# schema.net
KiCad netlist of a schematic drawn in Altium Designer
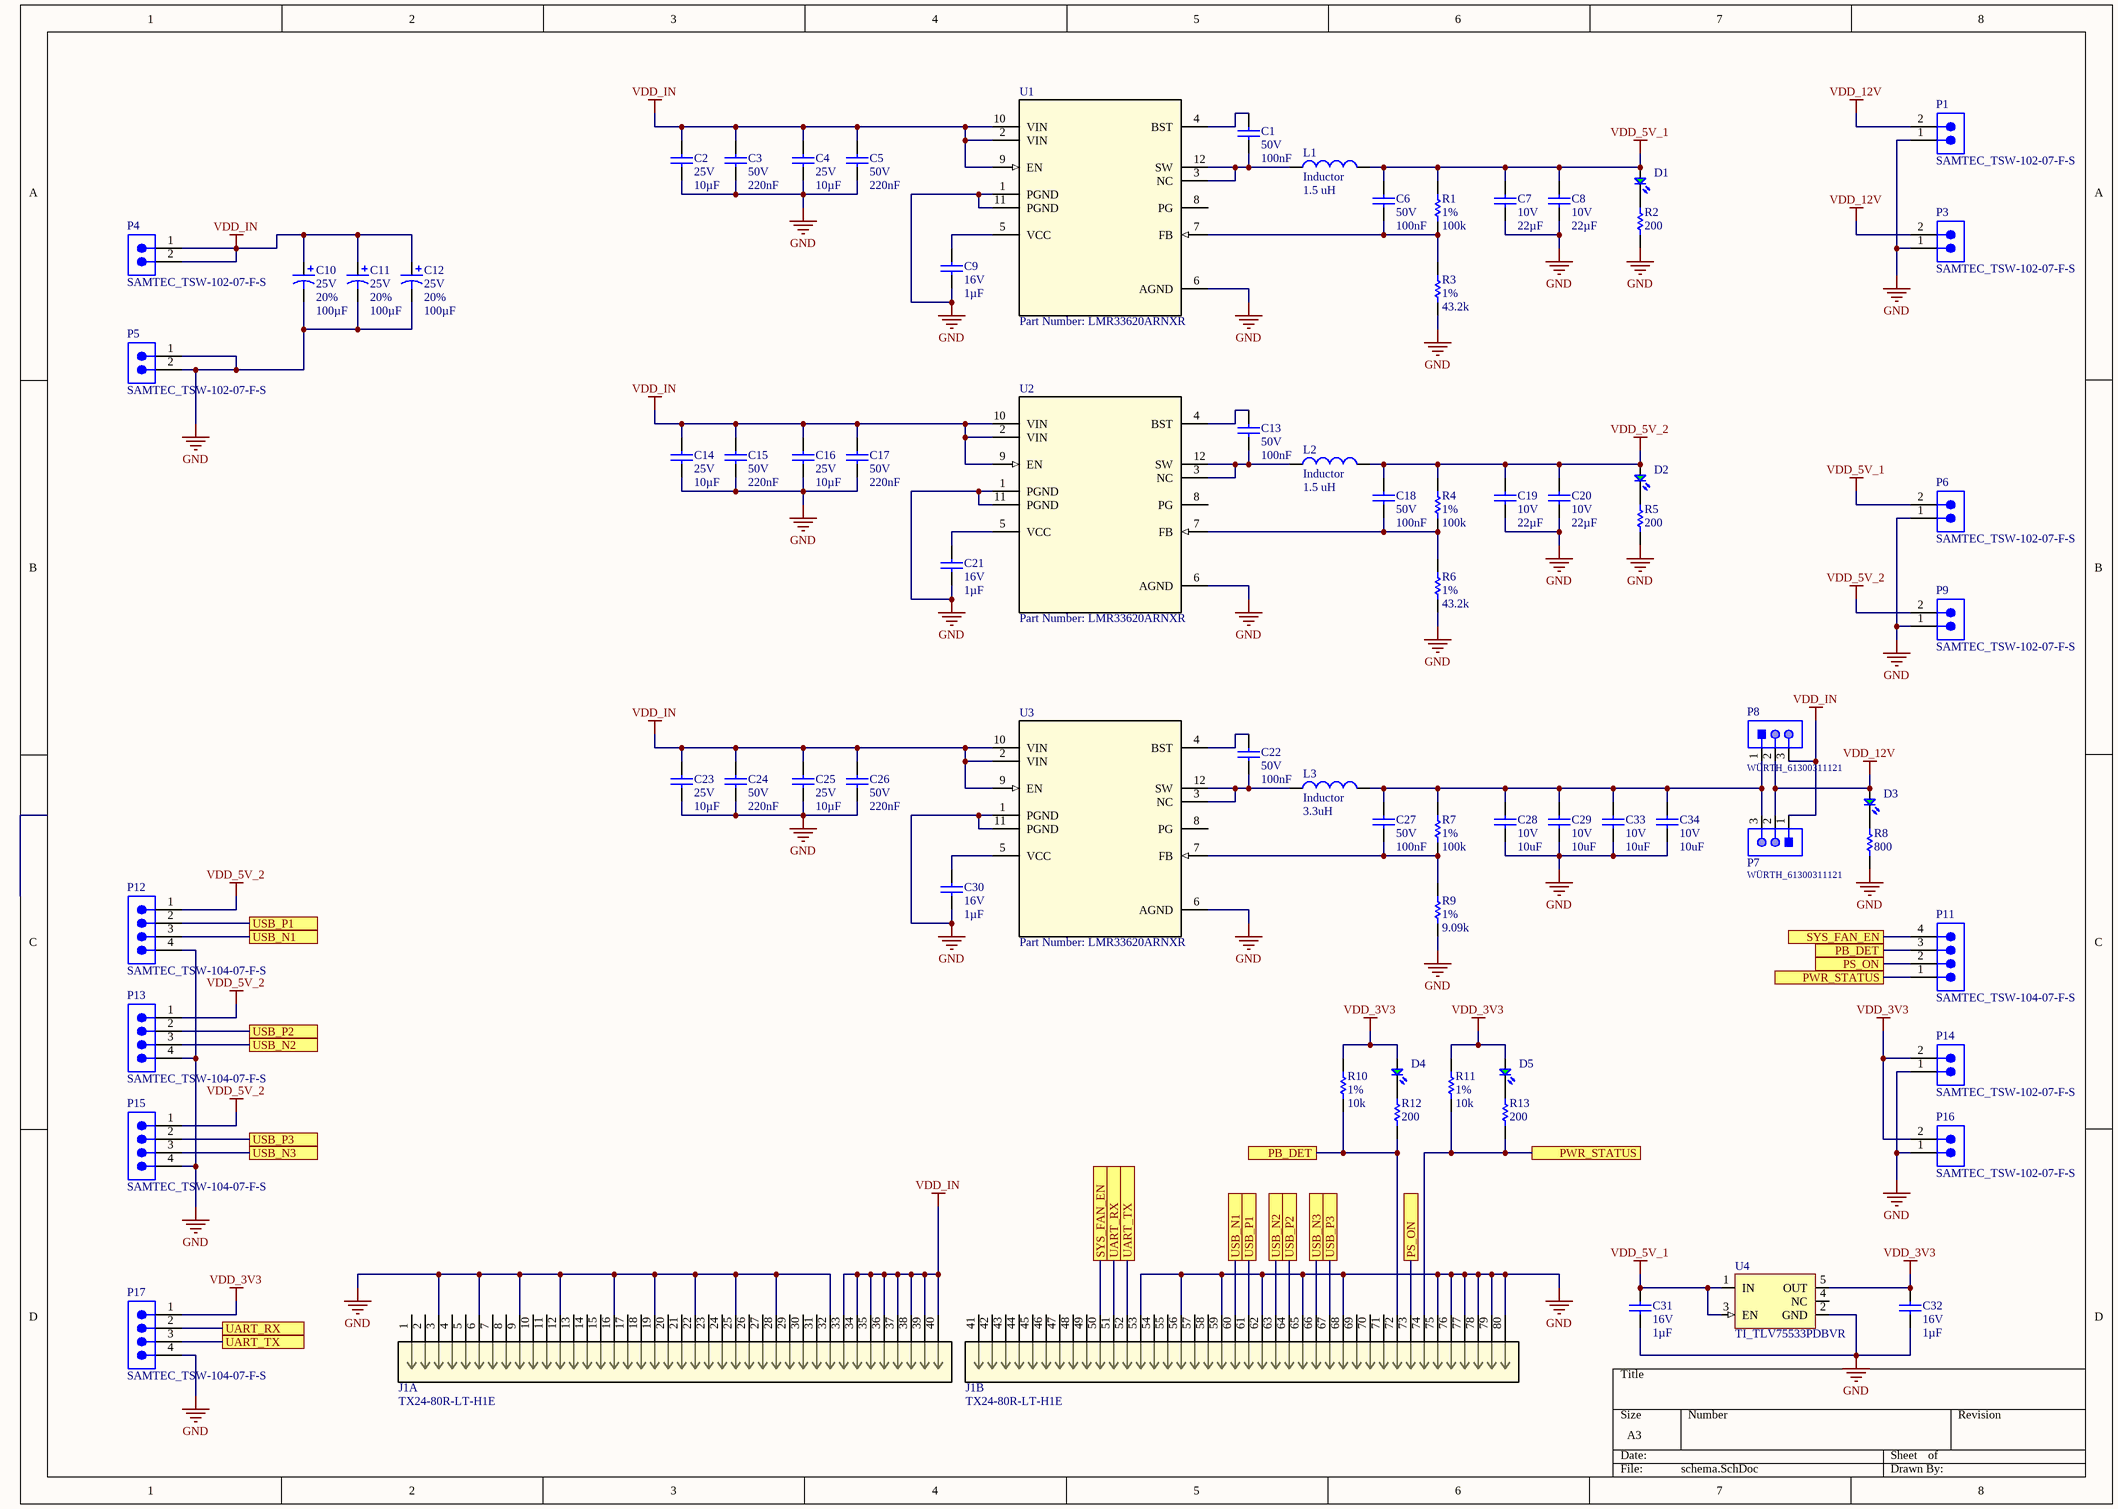
[diagram p0: schema.SchDoc]

(export (version "E")
  (design (tool "Eeschema 10.0.6"))
  (components
    (comp (ref "C1")
      (value "CAP MLCC 100nF 0402 10% 50V X5R")
      (footprint "C0402N")
      (description "Capacitor, MLCC, 100nF, 0402, 10%, 50V, X5R")
      (fields (field (name "VOLTAGE RATING") "50V") (field (name "COMPONENT VALUE") "100nF"))
      (libsource (lib "Ctek Sweden AB") (part "Non-polarised Capacitor"))
    )
    (comp (ref "C2")
      (value "CAP MLCC 10uF 0805 10% 25V X5R")
      (footprint "C0805N")
      (description "Capacitor, MLCC, 10uF, 0805, 10%, 25V, X5R")
      (fields (field (name "VOLTAGE RATING") "25V") (field (name "COMPONENT VALUE") "10µF"))
      (libsource (lib "Ctek Sweden AB") (part "Non-polarised Capacitor"))
    )
    (comp (ref "C3")
      (value "CAP MLCC 100nF 0402 10% 50V X5R")
      (footprint "C0402N")
      (description "Capacitor, MLCC, 100nF, 0402, 10%, 50V, X5R")
      (fields (field (name "VOLTAGE RATING") "50V") (field (name "COMPONENT VALUE") "220nF"))
      (libsource (lib "Ctek Sweden AB") (part "Non-polarised Capacitor"))
    )
    (comp (ref "C4")
      (value "CAP MLCC 10uF 0805 10% 25V X5R")
      (footprint "C0805N")
      (description "Capacitor, MLCC, 10uF, 0805, 10%, 25V, X5R")
      (fields (field (name "VOLTAGE RATING") "25V") (field (name "COMPONENT VALUE") "10µF"))
      (libsource (lib "Ctek Sweden AB") (part "Non-polarised Capacitor"))
    )
    (comp (ref "C5")
      (value "CAP MLCC 100nF 0402 10% 50V X5R")
      (footprint "C0402N")
      (description "Capacitor, MLCC, 100nF, 0402, 10%, 50V, X5R")
      (fields (field (name "VOLTAGE RATING") "50V") (field (name "COMPONENT VALUE") "220nF"))
      (libsource (lib "Ctek Sweden AB") (part "Non-polarised Capacitor"))
    )
    (comp (ref "C6")
      (value "CAP MLCC 100nF 0402 10% 50V X5R")
      (footprint "C0402N")
      (description "Capacitor, MLCC, 100nF, 0402, 10%, 50V, X5R")
      (fields (field (name "VOLTAGE RATING") "50V") (field (name "COMPONENT VALUE") "100nF"))
      (libsource (lib "Ctek Sweden AB") (part "Non-polarised Capacitor"))
    )
    (comp (ref "C7")
      (value "CAP MLCC 22uF 0805 10% 10V X5R")
      (footprint "C0805N")
      (description "Capacitor, MLCC, 22uF, 0805, 10%, 10V, X5R")
      (fields (field (name "VOLTAGE RATING") "10V") (field (name "COMPONENT VALUE") "22µF"))
      (libsource (lib "Ctek Sweden AB") (part "Non-polarised Capacitor"))
    )
    (comp (ref "C8")
      (value "CAP MLCC 22uF 0805 10% 10V X5R")
      (footprint "C0805N")
      (description "Capacitor, MLCC, 22uF, 0805, 10%, 10V, X5R")
      (fields (field (name "VOLTAGE RATING") "10V") (field (name "COMPONENT VALUE") "22µF"))
      (libsource (lib "Ctek Sweden AB") (part "Non-polarised Capacitor"))
    )
    (comp (ref "C9")
      (value "CAP MLCC 1uF 0402 10% 16V X5R")
      (footprint "C0402N")
      (description "Capacitor, MLCC, 1uF, 0402, 10%, 16V, X5R")
      (fields (field (name "VOLTAGE RATING") "16V") (field (name "COMPONENT VALUE") "1µF"))
      (libsource (lib "Ctek Sweden AB") (part "Non-polarised Capacitor"))
    )
    (comp (ref "C10")
      (value "ECAP 100uF radial 20% 25V 0.7mohm")
      (footprint "New footprint 1")
      (description "Electrolytic capacitor, 100uF, radial, 20%, 25V, 0.7mohm")
      (fields
        (field (name "VOLTAGE RATING") "25V")
        (field (name "COMPONENT TOLERANCE") "20%")
        (field (name "COMPONENT VALUE") "100µF")
      )
      (libsource (lib "Ctek Sweden AB") (part "Polarised Capacitor"))
    )
    (comp (ref "C11")
      (value "ECAP 100uF radial 20% 25V 0.7mohm")
      (footprint "New footprint 1")
      (description "Electrolytic capacitor, 100uF, radial, 20%, 25V, 0.7mohm")
      (fields
        (field (name "VOLTAGE RATING") "25V")
        (field (name "COMPONENT TOLERANCE") "20%")
        (field (name "COMPONENT VALUE") "100µF")
      )
      (libsource (lib "Ctek Sweden AB") (part "Polarised Capacitor"))
    )
    (comp (ref "C12")
      (value "ECAP 100uF radial 20% 25V 0.7mohm")
      (footprint "New footprint 1")
      (description "Electrolytic capacitor, 100uF, radial, 20%, 25V, 0.7mohm")
      (fields
        (field (name "VOLTAGE RATING") "25V")
        (field (name "COMPONENT TOLERANCE") "20%")
        (field (name "COMPONENT VALUE") "100µF")
      )
      (libsource (lib "Ctek Sweden AB") (part "Polarised Capacitor"))
    )
    (comp (ref "C13")
      (value "CAP MLCC 100nF 0402 10% 50V X5R")
      (footprint "C0402N")
      (description "Capacitor, MLCC, 100nF, 0402, 10%, 50V, X5R")
      (fields (field (name "VOLTAGE RATING") "50V") (field (name "COMPONENT VALUE") "100nF"))
      (libsource (lib "Ctek Sweden AB") (part "Non-polarised Capacitor"))
    )
    (comp (ref "C14")
      (value "CAP MLCC 10uF 0805 10% 25V X5R")
      (footprint "C0805N")
      (description "Capacitor, MLCC, 10uF, 0805, 10%, 25V, X5R")
      (fields (field (name "VOLTAGE RATING") "25V") (field (name "COMPONENT VALUE") "10µF"))
      (libsource (lib "Ctek Sweden AB") (part "Non-polarised Capacitor"))
    )
    (comp (ref "C15")
      (value "CAP MLCC 100nF 0402 10% 50V X5R")
      (footprint "C0402N")
      (description "Capacitor, MLCC, 100nF, 0402, 10%, 50V, X5R")
      (fields (field (name "VOLTAGE RATING") "50V") (field (name "COMPONENT VALUE") "220nF"))
      (libsource (lib "Ctek Sweden AB") (part "Non-polarised Capacitor"))
    )
    (comp (ref "C16")
      (value "CAP MLCC 10uF 0805 10% 25V X5R")
      (footprint "C0805N")
      (description "Capacitor, MLCC, 10uF, 0805, 10%, 25V, X5R")
      (fields (field (name "VOLTAGE RATING") "25V") (field (name "COMPONENT VALUE") "10µF"))
      (libsource (lib "Ctek Sweden AB") (part "Non-polarised Capacitor"))
    )
    (comp (ref "C17")
      (value "CAP MLCC 100nF 0402 10% 50V X5R")
      (footprint "C0402N")
      (description "Capacitor, MLCC, 100nF, 0402, 10%, 50V, X5R")
      (fields (field (name "VOLTAGE RATING") "50V") (field (name "COMPONENT VALUE") "220nF"))
      (libsource (lib "Ctek Sweden AB") (part "Non-polarised Capacitor"))
    )
    (comp (ref "C18")
      (value "CAP MLCC 100nF 0402 10% 50V X5R")
      (footprint "C0402N")
      (description "Capacitor, MLCC, 100nF, 0402, 10%, 50V, X5R")
      (fields (field (name "VOLTAGE RATING") "50V") (field (name "COMPONENT VALUE") "100nF"))
      (libsource (lib "Ctek Sweden AB") (part "Non-polarised Capacitor"))
    )
    (comp (ref "C19")
      (value "CAP MLCC 22uF 0805 10% 10V X5R")
      (footprint "C0805N")
      (description "Capacitor, MLCC, 22uF, 0805, 10%, 10V, X5R")
      (fields (field (name "VOLTAGE RATING") "10V") (field (name "COMPONENT VALUE") "22µF"))
      (libsource (lib "Ctek Sweden AB") (part "Non-polarised Capacitor"))
    )
    (comp (ref "C20")
      (value "CAP MLCC 22uF 0805 10% 10V X5R")
      (footprint "C0805N")
      (description "Capacitor, MLCC, 22uF, 0805, 10%, 10V, X5R")
      (fields (field (name "VOLTAGE RATING") "10V") (field (name "COMPONENT VALUE") "22µF"))
      (libsource (lib "Ctek Sweden AB") (part "Non-polarised Capacitor"))
    )
    (comp (ref "C21")
      (value "CAP MLCC 1uF 0402 10% 16V X5R")
      (footprint "C0402N")
      (description "Capacitor, MLCC, 1uF, 0402, 10%, 16V, X5R")
      (fields (field (name "VOLTAGE RATING") "16V") (field (name "COMPONENT VALUE") "1µF"))
      (libsource (lib "Ctek Sweden AB") (part "Non-polarised Capacitor"))
    )
    (comp (ref "C22")
      (value "CAP MLCC 100nF 0402 10% 50V X5R")
      (footprint "C0402N")
      (description "Capacitor, MLCC, 100nF, 0402, 10%, 50V, X5R")
      (fields (field (name "VOLTAGE RATING") "50V") (field (name "COMPONENT VALUE") "100nF"))
      (libsource (lib "Ctek Sweden AB") (part "Non-polarised Capacitor"))
    )
    (comp (ref "C23")
      (value "CAP MLCC 10uF 0805 10% 25V X5R")
      (footprint "C0805N")
      (description "Capacitor, MLCC, 10uF, 0805, 10%, 25V, X5R")
      (fields (field (name "VOLTAGE RATING") "25V") (field (name "COMPONENT VALUE") "10µF"))
      (libsource (lib "Ctek Sweden AB") (part "Non-polarised Capacitor"))
    )
    (comp (ref "C24")
      (value "CAP MLCC 100nF 0402 10% 50V X5R")
      (footprint "C0402N")
      (description "Capacitor, MLCC, 100nF, 0402, 10%, 50V, X5R")
      (fields (field (name "VOLTAGE RATING") "50V") (field (name "COMPONENT VALUE") "220nF"))
      (libsource (lib "Ctek Sweden AB") (part "Non-polarised Capacitor"))
    )
    (comp (ref "C25")
      (value "CAP MLCC 10uF 0805 10% 25V X5R")
      (footprint "C0805N")
      (description "Capacitor, MLCC, 10uF, 0805, 10%, 25V, X5R")
      (fields (field (name "VOLTAGE RATING") "25V") (field (name "COMPONENT VALUE") "10µF"))
      (libsource (lib "Ctek Sweden AB") (part "Non-polarised Capacitor"))
    )
    (comp (ref "C26")
      (value "CAP MLCC 100nF 0402 10% 50V X5R")
      (footprint "C0402N")
      (description "Capacitor, MLCC, 100nF, 0402, 10%, 50V, X5R")
      (fields (field (name "VOLTAGE RATING") "50V") (field (name "COMPONENT VALUE") "220nF"))
      (libsource (lib "Ctek Sweden AB") (part "Non-polarised Capacitor"))
    )
    (comp (ref "C27")
      (value "CAP MLCC 100nF 0402 10% 50V X5R")
      (footprint "C0402N")
      (description "Capacitor, MLCC, 100nF, 0402, 10%, 50V, X5R")
      (fields (field (name "VOLTAGE RATING") "50V") (field (name "COMPONENT VALUE") "100nF"))
      (libsource (lib "Ctek Sweden AB") (part "Non-polarised Capacitor"))
    )
    (comp (ref "C28")
      (value "CAP MLCC 22uF 0805 10% 10V X5R")
      (footprint "C0805N")
      (description "Capacitor, MLCC, 22uF, 0805, 10%, 10V, X5R")
      (fields (field (name "VOLTAGE RATING") "10V") (field (name "COMPONENT VALUE") "10uF"))
      (libsource (lib "Ctek Sweden AB") (part "Non-polarised Capacitor"))
    )
    (comp (ref "C29")
      (value "CAP MLCC 22uF 0805 10% 10V X5R")
      (footprint "C0805N")
      (description "Capacitor, MLCC, 22uF, 0805, 10%, 10V, X5R")
      (fields (field (name "VOLTAGE RATING") "10V") (field (name "COMPONENT VALUE") "10uF"))
      (libsource (lib "Ctek Sweden AB") (part "Non-polarised Capacitor"))
    )
    (comp (ref "C30")
      (value "CAP MLCC 1uF 0402 10% 16V X5R")
      (footprint "C0402N")
      (description "Capacitor, MLCC, 1uF, 0402, 10%, 16V, X5R")
      (fields (field (name "VOLTAGE RATING") "16V") (field (name "COMPONENT VALUE") "1µF"))
      (libsource (lib "Ctek Sweden AB") (part "Non-polarised Capacitor"))
    )
    (comp (ref "C31")
      (value "CAP MLCC 1uF 0402 10% 16V X5R")
      (footprint "C0402N")
      (description "Capacitor, MLCC, 1uF, 0402, 10%, 16V, X5R")
      (fields (field (name "VOLTAGE RATING") "16V") (field (name "COMPONENT VALUE") "1µF"))
      (libsource (lib "Ctek Sweden AB") (part "Non-polarised Capacitor"))
    )
    (comp (ref "C32")
      (value "CAP MLCC 1uF 0402 10% 16V X5R")
      (footprint "C0402N")
      (description "Capacitor, MLCC, 1uF, 0402, 10%, 16V, X5R")
      (fields (field (name "VOLTAGE RATING") "16V") (field (name "COMPONENT VALUE") "1µF"))
      (libsource (lib "Ctek Sweden AB") (part "Non-polarised Capacitor"))
    )
    (comp (ref "C33")
      (value "CAP MLCC 22uF 0805 10% 10V X5R")
      (footprint "C0805N")
      (description "Capacitor, MLCC, 22uF, 0805, 10%, 10V, X5R")
      (fields (field (name "VOLTAGE RATING") "10V") (field (name "COMPONENT VALUE") "10uF"))
      (libsource (lib "Ctek Sweden AB") (part "Non-polarised Capacitor"))
    )
    (comp (ref "C34")
      (value "CAP MLCC 22uF 0805 10% 10V X5R")
      (footprint "C0805N")
      (description "Capacitor, MLCC, 22uF, 0805, 10%, 10V, X5R")
      (fields (field (name "VOLTAGE RATING") "10V") (field (name "COMPONENT VALUE") "10uF"))
      (libsource (lib "Ctek Sweden AB") (part "Non-polarised Capacitor"))
    )
    (comp (ref "D1")
      (value "Hongbright_H2214AG72E0Z01")
      (footprint "New footprint 1")
      (description "Green LED, VFmax 3.6V")
      (libsource (lib "Ctek Sweden AB") (part "New symbol 1"))
    )
    (comp (ref "D2")
      (value "Hongbright_H2214AG72E0Z01")
      (footprint "New footprint 1")
      (description "Green LED, VFmax 3.6V")
      (libsource (lib "Ctek Sweden AB") (part "New symbol 1"))
    )
    (comp (ref "D3")
      (value "Hongbright_H2214AG72E0Z01")
      (footprint "New footprint 1")
      (description "Green LED, VFmax 3.6V")
      (libsource (lib "Ctek Sweden AB") (part "New symbol 1"))
    )
    (comp (ref "D4")
      (value "Hongbright_H2214AG72E0Z01")
      (footprint "New footprint 1")
      (description "Green LED, VFmax 3.6V")
      (libsource (lib "Ctek Sweden AB") (part "New symbol 1"))
    )
    (comp (ref "D5")
      (value "Hongbright_H2214AG72E0Z01")
      (footprint "New footprint 1")
      (description "Green LED, VFmax 3.6V")
      (libsource (lib "Ctek Sweden AB") (part "New symbol 1"))
    )
    (comp (ref "J1")
      (value "TX24-80R-LT-H1E")
      (footprint "CON80_2X40_MR_TX24_JAE")
      (description "No Description Available")
      (fields (field (name "COPYRIGHT") "Copyright (C) 2018 Accelerated Designs. All rights reserved"))
      (libsource (lib "tx24") (part "TX24-80R-LT-H1E"))
    )
    (comp (ref "L1")
      (value "Inductor")
      (footprint "INDC2016X10N")
      (fields (field (name "ALTIUM_VALUE") "1.5 uH") (field (name "PUBLISHER") "Altium Limited"))
      (libsource (lib "Miscellaneous Devices") (part "Inductor"))
    )
    (comp (ref "L2")
      (value "Inductor")
      (footprint "INDC2016X10N")
      (fields (field (name "ALTIUM_VALUE") "1.5 uH") (field (name "PUBLISHER") "Altium Limited"))
      (libsource (lib "Miscellaneous Devices") (part "Inductor"))
    )
    (comp (ref "L3")
      (value "Inductor")
      (footprint "INDC2016X10N")
      (fields (field (name "ALTIUM_VALUE") "3.3uH") (field (name "PUBLISHER") "Altium Limited"))
      (libsource (lib "Miscellaneous Devices") (part "Inductor"))
    )
    (comp (ref "P1")
      (value "SAMTEC_TSW-102-07-F-S")
      (footprint "SAMTEC-TSW-102-07-X-S")
      (description "CONN HEADER VERT 2POS 2.54MM")
      (libsource (lib "Ctek Sweden AB") (part "CONN2"))
    )
    (comp (ref "P3")
      (value "SAMTEC_TSW-102-07-F-S")
      (footprint "SAMTEC-TSW-102-07-X-S")
      (description "CONN HEADER VERT 2POS 2.54MM")
      (libsource (lib "Ctek Sweden AB") (part "CONN2"))
    )
    (comp (ref "P4")
      (value "SAMTEC_TSW-102-07-F-S")
      (footprint "SAMTEC-TSW-102-07-X-S")
      (description "CONN HEADER VERT 2POS 2.54MM")
      (libsource (lib "Ctek Sweden AB") (part "CONN2"))
    )
    (comp (ref "P5")
      (value "SAMTEC_TSW-102-07-F-S")
      (footprint "SAMTEC-TSW-102-07-X-S")
      (description "CONN HEADER VERT 2POS 2.54MM")
      (libsource (lib "Ctek Sweden AB") (part "CONN2"))
    )
    (comp (ref "P6")
      (value "SAMTEC_TSW-102-07-F-S")
      (footprint "SAMTEC-TSW-102-07-X-S")
      (description "CONN HEADER VERT 2POS 2.54MM")
      (libsource (lib "Ctek Sweden AB") (part "CONN2"))
    )
    (comp (ref "P7")
      (value "WÜRTH_61300311121")
      (footprint "61300311121")
      (libsource (lib "") (part "WE-CN-1P-M-R3_1"))
    )
    (comp (ref "P8")
      (value "WÜRTH_61300311121")
      (footprint "61300311121")
      (libsource (lib "Ctek Sweden AB") (part "WE-CN-1P-M-R3"))
    )
    (comp (ref "P9")
      (value "SAMTEC_TSW-102-07-F-S")
      (footprint "SAMTEC-TSW-102-07-X-S")
      (description "CONN HEADER VERT 2POS 2.54MM")
      (libsource (lib "Ctek Sweden AB") (part "CONN2"))
    )
    (comp (ref "P11")
      (value "SAMTEC_TSW-104-07-F-S")
      (footprint "SAMTEC-TSW-104-07-X-S")
      (description "CONN HEADER VERT 4POS 2.54MM")
      (libsource (lib "Ctek Sweden AB") (part "CONN4"))
    )
    (comp (ref "P12")
      (value "SAMTEC_TSW-104-07-F-S")
      (footprint "SAMTEC-TSW-104-07-X-S")
      (description "CONN HEADER VERT 4POS 2.54MM")
      (libsource (lib "Ctek Sweden AB") (part "CONN4"))
    )
    (comp (ref "P13")
      (value "SAMTEC_TSW-104-07-F-S")
      (footprint "SAMTEC-TSW-104-07-X-S")
      (description "CONN HEADER VERT 4POS 2.54MM")
      (libsource (lib "Ctek Sweden AB") (part "CONN4"))
    )
    (comp (ref "P14")
      (value "SAMTEC_TSW-102-07-F-S")
      (footprint "SAMTEC-TSW-102-07-X-S")
      (description "CONN HEADER VERT 2POS 2.54MM")
      (libsource (lib "Ctek Sweden AB") (part "CONN2"))
    )
    (comp (ref "P15")
      (value "SAMTEC_TSW-104-07-F-S")
      (footprint "SAMTEC-TSW-104-07-X-S")
      (description "CONN HEADER VERT 4POS 2.54MM")
      (libsource (lib "Ctek Sweden AB") (part "CONN4"))
    )
    (comp (ref "P16")
      (value "SAMTEC_TSW-102-07-F-S")
      (footprint "SAMTEC-TSW-102-07-X-S")
      (description "CONN HEADER VERT 2POS 2.54MM")
      (libsource (lib "Ctek Sweden AB") (part "CONN2"))
    )
    (comp (ref "P17")
      (value "SAMTEC_TSW-104-07-F-S")
      (footprint "SAMTEC-TSW-104-07-X-S")
      (description "CONN HEADER VERT 4POS 2.54MM")
      (libsource (lib "Ctek Sweden AB") (part "CONN4"))
    )
    (comp (ref "R1")
      (value "RES 100k 0402 1% 63mW")
      (footprint "R0402N")
      (description "Resistor, 100k, 0402, 1%, 63mW")
      (fields (field (name "COMPONENT TOLERANCE") "1%") (field (name "COMPONENT VALUE") "100k"))
      (libsource (lib "Ctek Sweden AB") (part "Resistor"))
    )
    (comp (ref "R2")
      (value "RES 100k 0402 1% 63mW")
      (footprint "R0402N")
      (description "Resistor, 100k, 0402, 1%, 63mW")
      (fields (field (name "COMPONENT VALUE") "200"))
      (libsource (lib "Ctek Sweden AB") (part "Resistor"))
    )
    (comp (ref "R3")
      (value "RES 100k 0402 1% 63mW")
      (footprint "R0402N")
      (description "Resistor, 100k, 0402, 1%, 63mW")
      (fields (field (name "COMPONENT TOLERANCE") "1%") (field (name "COMPONENT VALUE") "43.2k"))
      (libsource (lib "Ctek Sweden AB") (part "Resistor"))
    )
    (comp (ref "R4")
      (value "RES 100k 0402 1% 63mW")
      (footprint "R0402N")
      (description "Resistor, 100k, 0402, 1%, 63mW")
      (fields (field (name "COMPONENT TOLERANCE") "1%") (field (name "COMPONENT VALUE") "100k"))
      (libsource (lib "Ctek Sweden AB") (part "Resistor"))
    )
    (comp (ref "R5")
      (value "RES 100k 0402 1% 63mW")
      (footprint "R0402N")
      (description "Resistor, 100k, 0402, 1%, 63mW")
      (fields (field (name "COMPONENT VALUE") "200"))
      (libsource (lib "Ctek Sweden AB") (part "Resistor"))
    )
    (comp (ref "R6")
      (value "RES 100k 0402 1% 63mW")
      (footprint "R0402N")
      (description "Resistor, 100k, 0402, 1%, 63mW")
      (fields (field (name "COMPONENT TOLERANCE") "1%") (field (name "COMPONENT VALUE") "43.2k"))
      (libsource (lib "Ctek Sweden AB") (part "Resistor"))
    )
    (comp (ref "R7")
      (value "RES 100k 0402 1% 63mW")
      (footprint "R0402N")
      (description "Resistor, 100k, 0402, 1%, 63mW")
      (fields (field (name "COMPONENT TOLERANCE") "1%") (field (name "COMPONENT VALUE") "100k"))
      (libsource (lib "Ctek Sweden AB") (part "Resistor"))
    )
    (comp (ref "R8")
      (value "RES 100k 0402 1% 63mW")
      (footprint "R0402N")
      (description "Resistor, 100k, 0402, 1%, 63mW")
      (fields (field (name "COMPONENT VALUE") "800"))
      (libsource (lib "Ctek Sweden AB") (part "Resistor"))
    )
    (comp (ref "R9")
      (value "RES 100k 0402 1% 63mW")
      (footprint "R0402N")
      (description "Resistor, 100k, 0402, 1%, 63mW")
      (fields (field (name "COMPONENT TOLERANCE") "1%") (field (name "COMPONENT VALUE") "9.09k"))
      (libsource (lib "Ctek Sweden AB") (part "Resistor"))
    )
    (comp (ref "R10")
      (value "RES 100k 0402 1% 63mW")
      (footprint "R0402N")
      (description "Resistor, 100k, 0402, 1%, 63mW")
      (fields (field (name "COMPONENT TOLERANCE") "1%") (field (name "COMPONENT VALUE") "10k"))
      (libsource (lib "Ctek Sweden AB") (part "Resistor"))
    )
    (comp (ref "R11")
      (value "RES 100k 0402 1% 63mW")
      (footprint "R0402N")
      (description "Resistor, 100k, 0402, 1%, 63mW")
      (fields (field (name "COMPONENT TOLERANCE") "1%") (field (name "COMPONENT VALUE") "10k"))
      (libsource (lib "Ctek Sweden AB") (part "Resistor"))
    )
    (comp (ref "R12")
      (value "RES 100k 0402 1% 63mW")
      (footprint "R0402N")
      (description "Resistor, 100k, 0402, 1%, 63mW")
      (fields (field (name "COMPONENT VALUE") "200"))
      (libsource (lib "Ctek Sweden AB") (part "Resistor"))
    )
    (comp (ref "R13")
      (value "RES 100k 0402 1% 63mW")
      (footprint "R0402N")
      (description "Resistor, 100k, 0402, 1%, 63mW")
      (fields (field (name "COMPONENT VALUE") "200"))
      (libsource (lib "Ctek Sweden AB") (part "Resistor"))
    )
    (comp (ref "U1")
      (value "Part Number: LMR33620ARNXR")
      (footprint "RNX12")
      (description "SIMPLE SWITCHER® 3.8V to 36V, 2A Synchronous Buck Converter With Ultra-Low EMI")
      (fields (field (name "PARTNUMBER") "LMR33620ARNXR") (field (name "MANUFACTURER") "Texas Instruments"))
      (libsource (lib "power_regulators") (part "LMR33620"))
    )
    (comp (ref "U2")
      (value "Part Number: LMR33620ARNXR")
      (footprint "RNX12")
      (description "SIMPLE SWITCHER® 3.8V to 36V, 2A Synchronous Buck Converter With Ultra-Low EMI")
      (fields (field (name "PARTNUMBER") "LMR33620ARNXR") (field (name "MANUFACTURER") "Texas Instruments"))
      (libsource (lib "power_regulators") (part "LMR33620"))
    )
    (comp (ref "U3")
      (value "Part Number: LMR33620ARNXR")
      (footprint "RNX12")
      (description "SIMPLE SWITCHER® 3.8V to 36V, 2A Synchronous Buck Converter With Ultra-Low EMI")
      (fields (field (name "PARTNUMBER") "LMR33620ARNXR") (field (name "MANUFACTURER") "Texas Instruments"))
      (libsource (lib "power_regulators") (part "LMR33620"))
    )
    (comp (ref "U4")
      (value "TI_TLV75533PDBVR")
      (footprint "SOT23-5P95_280X145L45X40N")
      (description "Fixed Positive LDO Regulator, 3.3V, 0.238V Dropout, PDSO5")
      (libsource (lib "Ctek Sweden AB") (part "bc27d4aa6bca38f00d7b0ca125c90e0"))
    )
  )
  (nets
    (net (code "1") (name "/PB_DET") (class "Default")
      (node (ref "J1") (pin "72") (pinfunction "72_72") (pintype "passive"))
      (node (ref "P11") (pin "3") (pinfunction "3_3") (pintype "passive"))
      (node (ref "R10") (pin "1") (pinfunction "1_1") (pintype "passive"))
      (node (ref "R12") (pin "1") (pinfunction "1_1") (pintype "passive"))
    )
    (net (code "2") (name "/PS_ON") (class "Default")
      (node (ref "J1") (pin "73") (pinfunction "73_73") (pintype "passive"))
      (node (ref "P11") (pin "2") (pinfunction "2_2") (pintype "passive"))
    )
    (net (code "3") (name "/PWR_STATUS") (class "Default")
      (node (ref "J1") (pin "74") (pinfunction "74_74") (pintype "passive"))
      (node (ref "P11") (pin "1") (pinfunction "1_1") (pintype "passive"))
      (node (ref "R11") (pin "1") (pinfunction "1_1") (pintype "passive"))
      (node (ref "R13") (pin "1") (pinfunction "1_1") (pintype "passive"))
    )
    (net (code "4") (name "/SYS_FAN_EN") (class "Default")
      (node (ref "J1") (pin "50") (pinfunction "50_50") (pintype "passive"))
      (node (ref "P11") (pin "4") (pinfunction "4_4") (pintype "passive"))
    )
    (net (code "5") (name "/UART_RX") (class "Default")
      (node (ref "J1") (pin "51") (pinfunction "51_51") (pintype "passive"))
      (node (ref "P17") (pin "2") (pinfunction "2_2") (pintype "passive"))
    )
    (net (code "6") (name "/UART_TX") (class "Default")
      (node (ref "J1") (pin "52") (pinfunction "52_52") (pintype "passive"))
      (node (ref "P17") (pin "3") (pinfunction "3_3") (pintype "passive"))
    )
    (net (code "7") (name "/USB_N1") (class "Default")
      (node (ref "J1") (pin "60") (pinfunction "60_60") (pintype "passive"))
      (node (ref "P12") (pin "3") (pinfunction "3_3") (pintype "passive"))
    )
    (net (code "8") (name "/USB_N2") (class "Default")
      (node (ref "J1") (pin "63") (pinfunction "63_63") (pintype "passive"))
      (node (ref "P13") (pin "3") (pinfunction "3_3") (pintype "passive"))
    )
    (net (code "9") (name "/USB_N3") (class "Default")
      (node (ref "J1") (pin "66") (pinfunction "66_66") (pintype "passive"))
      (node (ref "P15") (pin "3") (pinfunction "3_3") (pintype "passive"))
    )
    (net (code "10") (name "/USB_P1") (class "Default")
      (node (ref "J1") (pin "61") (pinfunction "61_61") (pintype "passive"))
      (node (ref "P12") (pin "2") (pinfunction "2_2") (pintype "passive"))
    )
    (net (code "11") (name "/USB_P2") (class "Default")
      (node (ref "J1") (pin "64") (pinfunction "64_64") (pintype "passive"))
      (node (ref "P13") (pin "2") (pinfunction "2_2") (pintype "passive"))
    )
    (net (code "12") (name "/USB_P3") (class "Default")
      (node (ref "J1") (pin "67") (pinfunction "67_67") (pintype "passive"))
      (node (ref "P15") (pin "2") (pinfunction "2_2") (pintype "passive"))
    )
    (net (code "13") (name "GND") (class "Default")
      (node (ref "C10") (pin "2") (pinfunction "2_2") (pintype "passive"))
      (node (ref "C11") (pin "2") (pinfunction "2_2") (pintype "passive"))
      (node (ref "C12") (pin "2") (pinfunction "2_2") (pintype "passive"))
      (node (ref "C14") (pin "1") (pinfunction "1_1") (pintype "passive"))
      (node (ref "C15") (pin "1") (pinfunction "1_1") (pintype "passive"))
      (node (ref "C16") (pin "1") (pinfunction "1_1") (pintype "passive"))
      (node (ref "C17") (pin "1") (pinfunction "1_1") (pintype "passive"))
      (node (ref "C19") (pin "1") (pinfunction "1_1") (pintype "passive"))
      (node (ref "C2") (pin "1") (pinfunction "1_1") (pintype "passive"))
      (node (ref "C20") (pin "1") (pinfunction "1_1") (pintype "passive"))
      (node (ref "C21") (pin "1") (pinfunction "1_1") (pintype "passive"))
      (node (ref "C23") (pin "1") (pinfunction "1_1") (pintype "passive"))
      (node (ref "C24") (pin "1") (pinfunction "1_1") (pintype "passive"))
      (node (ref "C25") (pin "1") (pinfunction "1_1") (pintype "passive"))
      (node (ref "C26") (pin "1") (pinfunction "1_1") (pintype "passive"))
      (node (ref "C28") (pin "1") (pinfunction "1_1") (pintype "passive"))
      (node (ref "C29") (pin "1") (pinfunction "1_1") (pintype "passive"))
      (node (ref "C3") (pin "1") (pinfunction "1_1") (pintype "passive"))
      (node (ref "C30") (pin "1") (pinfunction "1_1") (pintype "passive"))
      (node (ref "C31") (pin "1") (pinfunction "1_1") (pintype "passive"))
      (node (ref "C32") (pin "1") (pinfunction "1_1") (pintype "passive"))
      (node (ref "C33") (pin "1") (pinfunction "1_1") (pintype "passive"))
      (node (ref "C34") (pin "1") (pinfunction "1_1") (pintype "passive"))
      (node (ref "C4") (pin "1") (pinfunction "1_1") (pintype "passive"))
      (node (ref "C5") (pin "1") (pinfunction "1_1") (pintype "passive"))
      (node (ref "C7") (pin "1") (pinfunction "1_1") (pintype "passive"))
      (node (ref "C8") (pin "1") (pinfunction "1_1") (pintype "passive"))
      (node (ref "C9") (pin "1") (pinfunction "1_1") (pintype "passive"))
      (node (ref "J1") (pin "12") (pinfunction "12_12") (pintype "passive"))
      (node (ref "J1") (pin "16") (pinfunction "16_16") (pintype "passive"))
      (node (ref "J1") (pin "19") (pinfunction "19_19") (pintype "passive"))
      (node (ref "J1") (pin "22") (pinfunction "22_22") (pintype "passive"))
      (node (ref "J1") (pin "25") (pinfunction "25_25") (pintype "passive"))
      (node (ref "J1") (pin "28") (pinfunction "28_28") (pintype "passive"))
      (node (ref "J1") (pin "3") (pinfunction "3_3") (pintype "passive"))
      (node (ref "J1") (pin "32") (pinfunction "32_32") (pintype "passive"))
      (node (ref "J1") (pin "53") (pinfunction "53_53") (pintype "passive"))
      (node (ref "J1") (pin "56") (pinfunction "56_56") (pintype "passive"))
      (node (ref "J1") (pin "59") (pinfunction "59_59") (pintype "passive"))
      (node (ref "J1") (pin "6") (pinfunction "6_6") (pintype "passive"))
      (node (ref "J1") (pin "62") (pinfunction "62_62") (pintype "passive"))
      (node (ref "J1") (pin "65") (pinfunction "65_65") (pintype "passive"))
      (node (ref "J1") (pin "68") (pinfunction "68_68") (pintype "passive"))
      (node (ref "J1") (pin "75") (pinfunction "75_75") (pintype "passive"))
      (node (ref "J1") (pin "76") (pinfunction "76_76") (pintype "passive"))
      (node (ref "J1") (pin "77") (pinfunction "77_77") (pintype "passive"))
      (node (ref "J1") (pin "78") (pinfunction "78_78") (pintype "passive"))
      (node (ref "J1") (pin "79") (pinfunction "79_79") (pintype "passive"))
      (node (ref "J1") (pin "80") (pinfunction "80_80") (pintype "passive"))
      (node (ref "J1") (pin "9") (pinfunction "9_9") (pintype "passive"))
      (node (ref "P1") (pin "1") (pinfunction "1_1") (pintype "passive"))
      (node (ref "P12") (pin "4") (pinfunction "4_4") (pintype "passive"))
      (node (ref "P13") (pin "4") (pinfunction "4_4") (pintype "passive"))
      (node (ref "P14") (pin "1") (pinfunction "1_1") (pintype "passive"))
      (node (ref "P15") (pin "4") (pinfunction "4_4") (pintype "passive"))
      (node (ref "P16") (pin "1") (pinfunction "1_1") (pintype "passive"))
      (node (ref "P17") (pin "4") (pinfunction "4_4") (pintype "passive"))
      (node (ref "P3") (pin "1") (pinfunction "1_1") (pintype "passive"))
      (node (ref "P5") (pin "1") (pinfunction "1_1") (pintype "passive"))
      (node (ref "P5") (pin "2") (pinfunction "2_2") (pintype "passive"))
      (node (ref "P6") (pin "1") (pinfunction "1_1") (pintype "passive"))
      (node (ref "P9") (pin "1") (pinfunction "1_1") (pintype "passive"))
      (node (ref "R2") (pin "1") (pinfunction "1_1") (pintype "passive"))
      (node (ref "R3") (pin "1") (pinfunction "1_1") (pintype "passive"))
      (node (ref "R5") (pin "1") (pinfunction "1_1") (pintype "passive"))
      (node (ref "R6") (pin "1") (pinfunction "1_1") (pintype "passive"))
      (node (ref "R8") (pin "1") (pinfunction "1_1") (pintype "passive"))
      (node (ref "R9") (pin "1") (pinfunction "1_1") (pintype "passive"))
      (node (ref "U1") (pin "1") (pinfunction "PGND_1") (pintype "power_in"))
      (node (ref "U1") (pin "11") (pinfunction "PGND_11") (pintype "power_in"))
      (node (ref "U1") (pin "6") (pinfunction "AGND_6") (pintype "power_in"))
      (node (ref "U2") (pin "1") (pinfunction "PGND_1") (pintype "power_in"))
      (node (ref "U2") (pin "11") (pinfunction "PGND_11") (pintype "power_in"))
      (node (ref "U2") (pin "6") (pinfunction "AGND_6") (pintype "power_in"))
      (node (ref "U3") (pin "1") (pinfunction "PGND_1") (pintype "power_in"))
      (node (ref "U3") (pin "11") (pinfunction "PGND_11") (pintype "power_in"))
      (node (ref "U3") (pin "6") (pinfunction "AGND_6") (pintype "power_in"))
      (node (ref "U4") (pin "2") (pinfunction "GND_2") (pintype "power_in"))
    )
    (net (code "14") (name "Net-(C27-Pad2)") (class "Default")
      (node (ref "C27") (pin "2") (pinfunction "2_2") (pintype "passive"))
      (node (ref "C28") (pin "2") (pinfunction "2_2") (pintype "passive"))
      (node (ref "C29") (pin "2") (pinfunction "2_2") (pintype "passive"))
      (node (ref "C33") (pin "2") (pinfunction "2_2") (pintype "passive"))
      (node (ref "C34") (pin "2") (pinfunction "2_2") (pintype "passive"))
      (node (ref "L3") (pin "2") (pinfunction "2_2") (pintype "passive"))
      (node (ref "P7") (pin "3") (pinfunction "3_3") (pintype "passive"))
      (node (ref "P8") (pin "1") (pinfunction "1_1") (pintype "passive"))
      (node (ref "R7") (pin "2") (pinfunction "2_2") (pintype "passive"))
    )
    (net (code "15") (name "Net-(D1--)") (class "Default")
      (node (ref "D1") (pin "2") (pinfunction "-_2") (pintype "passive"))
      (node (ref "R2") (pin "2") (pinfunction "2_2") (pintype "passive"))
    )
    (net (code "16") (name "Net-(D2--)") (class "Default")
      (node (ref "D2") (pin "2") (pinfunction "-_2") (pintype "passive"))
      (node (ref "R5") (pin "2") (pinfunction "2_2") (pintype "passive"))
    )
    (net (code "17") (name "Net-(D3--)") (class "Default")
      (node (ref "D3") (pin "2") (pinfunction "-_2") (pintype "passive"))
      (node (ref "R8") (pin "2") (pinfunction "2_2") (pintype "passive"))
    )
    (net (code "18") (name "Net-(D4--)") (class "Default")
      (node (ref "D4") (pin "2") (pinfunction "-_2") (pintype "passive"))
      (node (ref "R12") (pin "2") (pinfunction "2_2") (pintype "passive"))
    )
    (net (code "19") (name "Net-(D5--)") (class "Default")
      (node (ref "D5") (pin "2") (pinfunction "-_2") (pintype "passive"))
      (node (ref "R13") (pin "2") (pinfunction "2_2") (pintype "passive"))
    )
    (net (code "20") (name "Net-(U1-BST)") (class "Default")
      (node (ref "C1") (pin "2") (pinfunction "2_2") (pintype "passive"))
      (node (ref "U1") (pin "4") (pinfunction "BST_4") (pintype "passive"))
    )
    (net (code "21") (name "Net-(U1-FB)") (class "Default")
      (node (ref "C6") (pin "1") (pinfunction "1_1") (pintype "passive"))
      (node (ref "R1") (pin "1") (pinfunction "1_1") (pintype "passive"))
      (node (ref "R3") (pin "2") (pinfunction "2_2") (pintype "passive"))
      (node (ref "U1") (pin "7") (pinfunction "FB_7") (pintype "input"))
    )
    (net (code "22") (name "Net-(U1-NC)") (class "Default")
      (node (ref "C1") (pin "1") (pinfunction "1_1") (pintype "passive"))
      (node (ref "L1") (pin "1") (pinfunction "1_1") (pintype "passive"))
      (node (ref "U1") (pin "12") (pinfunction "SW_12") (pintype "power_in"))
      (node (ref "U1") (pin "3") (pinfunction "NC_3") (pintype "passive"))
    )
    (net (code "23") (name "Net-(U1-VCC)") (class "Default")
      (node (ref "C9") (pin "2") (pinfunction "2_2") (pintype "passive"))
      (node (ref "U1") (pin "5") (pinfunction "VCC_5") (pintype "power_in"))
    )
    (net (code "24") (name "Net-(U2-BST)") (class "Default")
      (node (ref "C13") (pin "2") (pinfunction "2_2") (pintype "passive"))
      (node (ref "U2") (pin "4") (pinfunction "BST_4") (pintype "passive"))
    )
    (net (code "25") (name "Net-(U2-FB)") (class "Default")
      (node (ref "C18") (pin "1") (pinfunction "1_1") (pintype "passive"))
      (node (ref "R4") (pin "1") (pinfunction "1_1") (pintype "passive"))
      (node (ref "R6") (pin "2") (pinfunction "2_2") (pintype "passive"))
      (node (ref "U2") (pin "7") (pinfunction "FB_7") (pintype "input"))
    )
    (net (code "26") (name "Net-(U2-NC)") (class "Default")
      (node (ref "C13") (pin "1") (pinfunction "1_1") (pintype "passive"))
      (node (ref "L2") (pin "1") (pinfunction "1_1") (pintype "passive"))
      (node (ref "U2") (pin "12") (pinfunction "SW_12") (pintype "power_in"))
      (node (ref "U2") (pin "3") (pinfunction "NC_3") (pintype "passive"))
    )
    (net (code "27") (name "Net-(U2-VCC)") (class "Default")
      (node (ref "C21") (pin "2") (pinfunction "2_2") (pintype "passive"))
      (node (ref "U2") (pin "5") (pinfunction "VCC_5") (pintype "power_in"))
    )
    (net (code "28") (name "Net-(U3-BST)") (class "Default")
      (node (ref "C22") (pin "2") (pinfunction "2_2") (pintype "passive"))
      (node (ref "U3") (pin "4") (pinfunction "BST_4") (pintype "passive"))
    )
    (net (code "29") (name "Net-(U3-FB)") (class "Default")
      (node (ref "C27") (pin "1") (pinfunction "1_1") (pintype "passive"))
      (node (ref "R7") (pin "1") (pinfunction "1_1") (pintype "passive"))
      (node (ref "R9") (pin "2") (pinfunction "2_2") (pintype "passive"))
      (node (ref "U3") (pin "7") (pinfunction "FB_7") (pintype "input"))
    )
    (net (code "30") (name "Net-(U3-NC)") (class "Default")
      (node (ref "C22") (pin "1") (pinfunction "1_1") (pintype "passive"))
      (node (ref "L3") (pin "1") (pinfunction "1_1") (pintype "passive"))
      (node (ref "U3") (pin "12") (pinfunction "SW_12") (pintype "power_in"))
      (node (ref "U3") (pin "3") (pinfunction "NC_3") (pintype "passive"))
    )
    (net (code "31") (name "Net-(U3-VCC)") (class "Default")
      (node (ref "C30") (pin "2") (pinfunction "2_2") (pintype "passive"))
      (node (ref "U3") (pin "5") (pinfunction "VCC_5") (pintype "power_in"))
    )
    (net (code "32") (name "VDD_3V3") (class "Default")
      (node (ref "C32") (pin "2") (pinfunction "2_2") (pintype "passive"))
      (node (ref "D4") (pin "1") (pinfunction "+_1") (pintype "passive"))
      (node (ref "D5") (pin "1") (pinfunction "+_1") (pintype "passive"))
      (node (ref "P14") (pin "2") (pinfunction "2_2") (pintype "passive"))
      (node (ref "P16") (pin "2") (pinfunction "2_2") (pintype "passive"))
      (node (ref "P17") (pin "1") (pinfunction "1_1") (pintype "passive"))
      (node (ref "R10") (pin "2") (pinfunction "2_2") (pintype "passive"))
      (node (ref "R11") (pin "2") (pinfunction "2_2") (pintype "passive"))
      (node (ref "U4") (pin "5") (pinfunction "OUT_5") (pintype "power_in"))
    )
    (net (code "33") (name "VDD_5V_1") (class "Default")
      (node (ref "C31") (pin "2") (pinfunction "2_2") (pintype "passive"))
      (node (ref "C6") (pin "2") (pinfunction "2_2") (pintype "passive"))
      (node (ref "C7") (pin "2") (pinfunction "2_2") (pintype "passive"))
      (node (ref "C8") (pin "2") (pinfunction "2_2") (pintype "passive"))
      (node (ref "D1") (pin "1") (pinfunction "+_1") (pintype "passive"))
      (node (ref "L1") (pin "2") (pinfunction "2_2") (pintype "passive"))
      (node (ref "P6") (pin "2") (pinfunction "2_2") (pintype "passive"))
      (node (ref "R1") (pin "2") (pinfunction "2_2") (pintype "passive"))
      (node (ref "U4") (pin "1") (pinfunction "IN_1") (pintype "power_in"))
      (node (ref "U4") (pin "3") (pinfunction "EN_3") (pintype "input"))
    )
    (net (code "34") (name "VDD_5V_2") (class "Default")
      (node (ref "C18") (pin "2") (pinfunction "2_2") (pintype "passive"))
      (node (ref "C19") (pin "2") (pinfunction "2_2") (pintype "passive"))
      (node (ref "C20") (pin "2") (pinfunction "2_2") (pintype "passive"))
      (node (ref "D2") (pin "1") (pinfunction "+_1") (pintype "passive"))
      (node (ref "L2") (pin "2") (pinfunction "2_2") (pintype "passive"))
      (node (ref "P12") (pin "1") (pinfunction "1_1") (pintype "passive"))
      (node (ref "P13") (pin "1") (pinfunction "1_1") (pintype "passive"))
      (node (ref "P15") (pin "1") (pinfunction "1_1") (pintype "passive"))
      (node (ref "P9") (pin "2") (pinfunction "2_2") (pintype "passive"))
      (node (ref "R4") (pin "2") (pinfunction "2_2") (pintype "passive"))
    )
    (net (code "35") (name "VDD_12V") (class "Default")
      (node (ref "D3") (pin "1") (pinfunction "+_1") (pintype "passive"))
      (node (ref "P1") (pin "2") (pinfunction "2_2") (pintype "passive"))
      (node (ref "P3") (pin "2") (pinfunction "2_2") (pintype "passive"))
      (node (ref "P7") (pin "2") (pinfunction "2_2") (pintype "passive"))
      (node (ref "P8") (pin "2") (pinfunction "2_2") (pintype "passive"))
    )
    (net (code "36") (name "VDD_IN") (class "Default")
      (node (ref "C10") (pin "1") (pinfunction "1_1") (pintype "passive"))
      (node (ref "C11") (pin "1") (pinfunction "1_1") (pintype "passive"))
      (node (ref "C12") (pin "1") (pinfunction "1_1") (pintype "passive"))
      (node (ref "C14") (pin "2") (pinfunction "2_2") (pintype "passive"))
      (node (ref "C15") (pin "2") (pinfunction "2_2") (pintype "passive"))
      (node (ref "C16") (pin "2") (pinfunction "2_2") (pintype "passive"))
      (node (ref "C17") (pin "2") (pinfunction "2_2") (pintype "passive"))
      (node (ref "C2") (pin "2") (pinfunction "2_2") (pintype "passive"))
      (node (ref "C23") (pin "2") (pinfunction "2_2") (pintype "passive"))
      (node (ref "C24") (pin "2") (pinfunction "2_2") (pintype "passive"))
      (node (ref "C25") (pin "2") (pinfunction "2_2") (pintype "passive"))
      (node (ref "C26") (pin "2") (pinfunction "2_2") (pintype "passive"))
      (node (ref "C3") (pin "2") (pinfunction "2_2") (pintype "passive"))
      (node (ref "C4") (pin "2") (pinfunction "2_2") (pintype "passive"))
      (node (ref "C5") (pin "2") (pinfunction "2_2") (pintype "passive"))
      (node (ref "J1") (pin "33") (pinfunction "33_33") (pintype "passive"))
      (node (ref "J1") (pin "34") (pinfunction "34_34") (pintype "passive"))
      (node (ref "J1") (pin "35") (pinfunction "35_35") (pintype "passive"))
      (node (ref "J1") (pin "36") (pinfunction "36_36") (pintype "passive"))
      (node (ref "J1") (pin "37") (pinfunction "37_37") (pintype "passive"))
      (node (ref "J1") (pin "38") (pinfunction "38_38") (pintype "passive"))
      (node (ref "J1") (pin "39") (pinfunction "39_39") (pintype "passive"))
      (node (ref "J1") (pin "40") (pinfunction "40_40") (pintype "passive"))
      (node (ref "P4") (pin "1") (pinfunction "1_1") (pintype "passive"))
      (node (ref "P4") (pin "2") (pinfunction "2_2") (pintype "passive"))
      (node (ref "P7") (pin "1") (pinfunction "1_1") (pintype "passive"))
      (node (ref "P8") (pin "3") (pinfunction "3_3") (pintype "passive"))
      (node (ref "U1") (pin "10") (pinfunction "VIN_10") (pintype "power_in"))
      (node (ref "U1") (pin "2") (pinfunction "VIN_2") (pintype "power_in"))
      (node (ref "U1") (pin "9") (pinfunction "EN_9") (pintype "input"))
      (node (ref "U2") (pin "10") (pinfunction "VIN_10") (pintype "power_in"))
      (node (ref "U2") (pin "2") (pinfunction "VIN_2") (pintype "power_in"))
      (node (ref "U2") (pin "9") (pinfunction "EN_9") (pintype "input"))
      (node (ref "U3") (pin "10") (pinfunction "VIN_10") (pintype "power_in"))
      (node (ref "U3") (pin "2") (pinfunction "VIN_2") (pintype "power_in"))
      (node (ref "U3") (pin "9") (pinfunction "EN_9") (pintype "input"))
    )
    (net (code "37") (name "unconnected-(J1-Pad1)") (class "Default")
      (node (ref "J1") (pin "1") (pinfunction "1_1") (pintype "passive"))
    )
    (net (code "38") (name "unconnected-(J1-Pad2)") (class "Default")
      (node (ref "J1") (pin "2") (pinfunction "2_2") (pintype "passive"))
    )
    (net (code "39") (name "unconnected-(J1-Pad4)") (class "Default")
      (node (ref "J1") (pin "4") (pinfunction "4_4") (pintype "passive"))
    )
    (net (code "40") (name "unconnected-(J1-Pad5)") (class "Default")
      (node (ref "J1") (pin "5") (pinfunction "5_5") (pintype "passive"))
    )
    (net (code "41") (name "unconnected-(J1-Pad7)") (class "Default")
      (node (ref "J1") (pin "7") (pinfunction "7_7") (pintype "passive"))
    )
    (net (code "42") (name "unconnected-(J1-Pad8)") (class "Default")
      (node (ref "J1") (pin "8") (pinfunction "8_8") (pintype "passive"))
    )
    (net (code "43") (name "unconnected-(J1-Pad10)") (class "Default")
      (node (ref "J1") (pin "10") (pinfunction "10_10") (pintype "passive"))
    )
    (net (code "44") (name "unconnected-(J1-Pad11)") (class "Default")
      (node (ref "J1") (pin "11") (pinfunction "11_11") (pintype "passive"))
    )
    (net (code "45") (name "unconnected-(J1-Pad13)") (class "Default")
      (node (ref "J1") (pin "13") (pinfunction "13_13") (pintype "passive"))
    )
    (net (code "46") (name "unconnected-(J1-Pad14)") (class "Default")
      (node (ref "J1") (pin "14") (pinfunction "14_14") (pintype "passive"))
    )
    (net (code "47") (name "unconnected-(J1-Pad15)") (class "Default")
      (node (ref "J1") (pin "15") (pinfunction "15_15") (pintype "passive"))
    )
    (net (code "48") (name "unconnected-(J1-Pad17)") (class "Default")
      (node (ref "J1") (pin "17") (pinfunction "17_17") (pintype "passive"))
    )
    (net (code "49") (name "unconnected-(J1-Pad18)") (class "Default")
      (node (ref "J1") (pin "18") (pinfunction "18_18") (pintype "passive"))
    )
    (net (code "50") (name "unconnected-(J1-Pad20)") (class "Default")
      (node (ref "J1") (pin "20") (pinfunction "20_20") (pintype "passive"))
    )
    (net (code "51") (name "unconnected-(J1-Pad21)") (class "Default")
      (node (ref "J1") (pin "21") (pinfunction "21_21") (pintype "passive"))
    )
    (net (code "52") (name "unconnected-(J1-Pad23)") (class "Default")
      (node (ref "J1") (pin "23") (pinfunction "23_23") (pintype "passive"))
    )
    (net (code "53") (name "unconnected-(J1-Pad24)") (class "Default")
      (node (ref "J1") (pin "24") (pinfunction "24_24") (pintype "passive"))
    )
    (net (code "54") (name "unconnected-(J1-Pad26)") (class "Default")
      (node (ref "J1") (pin "26") (pinfunction "26_26") (pintype "passive"))
    )
    (net (code "55") (name "unconnected-(J1-Pad27)") (class "Default")
      (node (ref "J1") (pin "27") (pinfunction "27_27") (pintype "passive"))
    )
    (net (code "56") (name "unconnected-(J1-Pad29)") (class "Default")
      (node (ref "J1") (pin "29") (pinfunction "29_29") (pintype "passive"))
    )
    (net (code "57") (name "unconnected-(J1-Pad30)") (class "Default")
      (node (ref "J1") (pin "30") (pinfunction "30_30") (pintype "passive"))
    )
    (net (code "58") (name "unconnected-(J1-Pad31)") (class "Default")
      (node (ref "J1") (pin "31") (pinfunction "31_31") (pintype "passive"))
    )
    (net (code "59") (name "unconnected-(J1-Pad41)") (class "Default")
      (node (ref "J1") (pin "41") (pinfunction "41_41") (pintype "passive"))
    )
    (net (code "60") (name "unconnected-(J1-Pad42)") (class "Default")
      (node (ref "J1") (pin "42") (pinfunction "42_42") (pintype "passive"))
    )
    (net (code "61") (name "unconnected-(J1-Pad43)") (class "Default")
      (node (ref "J1") (pin "43") (pinfunction "43_43") (pintype "passive"))
    )
    (net (code "62") (name "unconnected-(J1-Pad44)") (class "Default")
      (node (ref "J1") (pin "44") (pinfunction "44_44") (pintype "passive"))
    )
    (net (code "63") (name "unconnected-(J1-Pad45)") (class "Default")
      (node (ref "J1") (pin "45") (pinfunction "45_45") (pintype "passive"))
    )
    (net (code "64") (name "unconnected-(J1-Pad46)") (class "Default")
      (node (ref "J1") (pin "46") (pinfunction "46_46") (pintype "passive"))
    )
    (net (code "65") (name "unconnected-(J1-Pad47)") (class "Default")
      (node (ref "J1") (pin "47") (pinfunction "47_47") (pintype "passive"))
    )
    (net (code "66") (name "unconnected-(J1-Pad48)") (class "Default")
      (node (ref "J1") (pin "48") (pinfunction "48_48") (pintype "passive"))
    )
    (net (code "67") (name "unconnected-(J1-Pad49)") (class "Default")
      (node (ref "J1") (pin "49") (pinfunction "49_49") (pintype "passive"))
    )
    (net (code "68") (name "unconnected-(J1-Pad54)") (class "Default")
      (node (ref "J1") (pin "54") (pinfunction "54_54") (pintype "passive"))
    )
    (net (code "69") (name "unconnected-(J1-Pad55)") (class "Default")
      (node (ref "J1") (pin "55") (pinfunction "55_55") (pintype "passive"))
    )
    (net (code "70") (name "unconnected-(J1-Pad57)") (class "Default")
      (node (ref "J1") (pin "57") (pinfunction "57_57") (pintype "passive"))
    )
    (net (code "71") (name "unconnected-(J1-Pad58)") (class "Default")
      (node (ref "J1") (pin "58") (pinfunction "58_58") (pintype "passive"))
    )
    (net (code "72") (name "unconnected-(J1-Pad69)") (class "Default")
      (node (ref "J1") (pin "69") (pinfunction "69_69") (pintype "passive"))
    )
    (net (code "73") (name "unconnected-(J1-Pad70)") (class "Default")
      (node (ref "J1") (pin "70") (pinfunction "70_70") (pintype "passive"))
    )
    (net (code "74") (name "unconnected-(J1-Pad71)") (class "Default")
      (node (ref "J1") (pin "71") (pinfunction "71_71") (pintype "passive"))
    )
    (net (code "75") (name "unconnected-(U1-PG-Pad8)") (class "Default")
      (node (ref "U1") (pin "8") (pinfunction "PG_8") (pintype "open_collector"))
    )
    (net (code "76") (name "unconnected-(U2-PG-Pad8)") (class "Default")
      (node (ref "U2") (pin "8") (pinfunction "PG_8") (pintype "open_collector"))
    )
    (net (code "77") (name "unconnected-(U3-PG-Pad8)") (class "Default")
      (node (ref "U3") (pin "8") (pinfunction "PG_8") (pintype "open_collector"))
    )
    (net (code "78") (name "unconnected-(U4-NC-Pad4)") (class "Default")
      (node (ref "U4") (pin "4") (pinfunction "NC_4") (pintype "passive"))
    )
  )
)
